# adapter.net
KiCad netlist of a schematic drawn in EAGLE
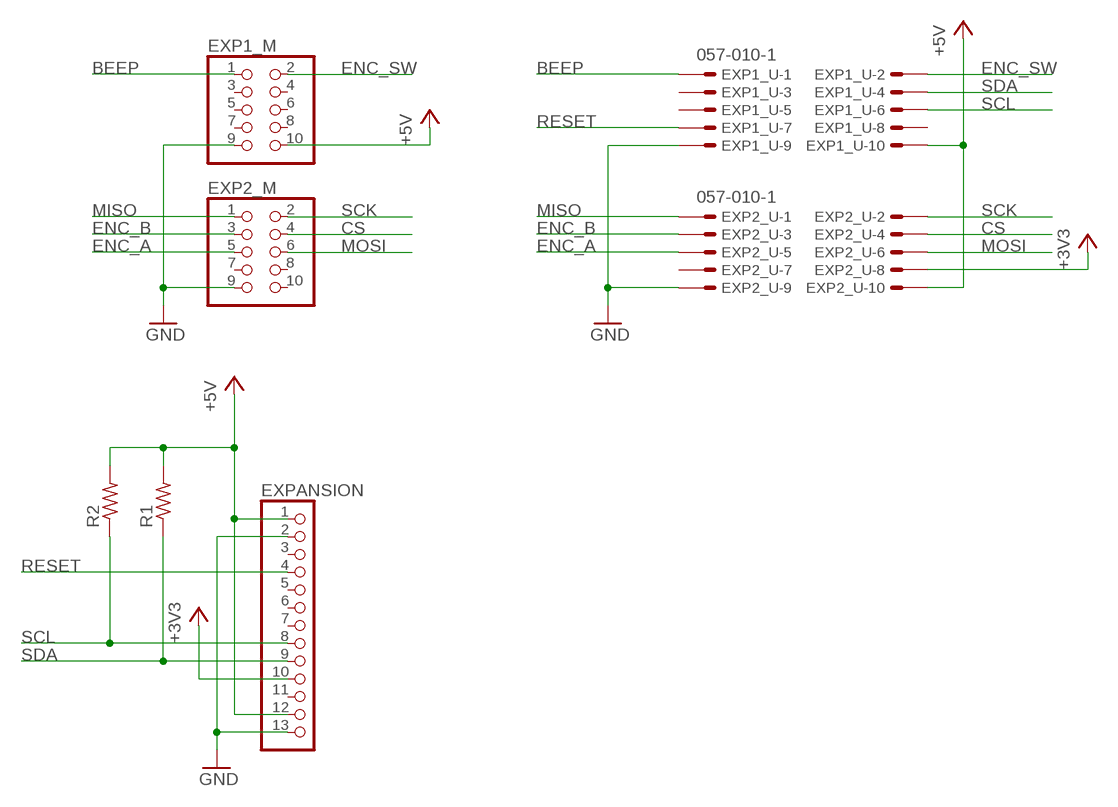
[diagram p0: schematic, sheet 1]

(export (version "E")
  (design (tool "Eeschema 10.0.6"))
  (components
    (comp (ref "EXP1_M")
      (value "PINHD-2X5")
      (footprint "eagle-import:2X05")
      (libsource (lib "eagle-import") (part "PINHD-2X5"))
    )
    (comp (ref "EXP1_U")
      (value "057-010-1")
      (footprint "eagle-import:057-010-1")
      (libsource (lib "eagle-import") (part "057-010-1"))
    )
    (comp (ref "EXP2_M")
      (value "PINHD-2X5")
      (footprint "eagle-import:2X05")
      (libsource (lib "eagle-import") (part "PINHD-2X5"))
    )
    (comp (ref "EXP2_U")
      (value "057-010-1")
      (footprint "eagle-import:057-010-1")
      (libsource (lib "eagle-import") (part "057-010-1"))
    )
    (comp (ref "EXPANSION")
      (value "PINHD-1X13")
      (footprint "eagle-import:1X13")
      (libsource (lib "eagle-import") (part "PINHD-1X13"))
    )
    (comp (ref "R1")
      (value "R-US_0204/7")
      (footprint "eagle-import:0204_7")
      (libsource (lib "eagle-import") (part "R-US_0204/7"))
    )
    (comp (ref "R2")
      (value "R-US_0204/7")
      (footprint "eagle-import:0204_7")
      (libsource (lib "eagle-import") (part "R-US_0204/7"))
    )
  )
  (nets
    (net (code "1") (name "+3V3") (class "Default")
      (node (ref "EXP2_U") (pin "8") (pinfunction "S_8") (pintype "passive"))
      (node (ref "EXPANSION") (pin "10") (pinfunction "10_10") (pintype "passive"))
    )
    (net (code "2") (name "+5V") (class "Default")
      (node (ref "EXP1_M") (pin "10") (pinfunction "10_10") (pintype "passive"))
      (node (ref "EXP1_U") (pin "10") (pinfunction "S_10") (pintype "passive"))
      (node (ref "EXP2_U") (pin "10") (pinfunction "S_10") (pintype "passive"))
      (node (ref "EXPANSION") (pin "1") (pinfunction "1_1") (pintype "passive"))
      (node (ref "EXPANSION") (pin "12") (pinfunction "12_12") (pintype "passive"))
      (node (ref "R1") (pin "2") (pinfunction "2_2") (pintype "passive"))
      (node (ref "R2") (pin "2") (pinfunction "2_2") (pintype "passive"))
    )
    (net (code "3") (name "/BEEP") (class "Default")
      (node (ref "EXP1_M") (pin "1") (pinfunction "1_1") (pintype "passive"))
      (node (ref "EXP1_U") (pin "1") (pinfunction "S_1") (pintype "passive"))
    )
    (net (code "4") (name "/CS") (class "Default")
      (node (ref "EXP2_M") (pin "4") (pinfunction "4_4") (pintype "passive"))
      (node (ref "EXP2_U") (pin "4") (pinfunction "S_4") (pintype "passive"))
    )
    (net (code "5") (name "/ENC_A") (class "Default")
      (node (ref "EXP2_M") (pin "5") (pinfunction "5_5") (pintype "passive"))
      (node (ref "EXP2_U") (pin "5") (pinfunction "S_5") (pintype "passive"))
    )
    (net (code "6") (name "/ENC_B") (class "Default")
      (node (ref "EXP2_M") (pin "3") (pinfunction "3_3") (pintype "passive"))
      (node (ref "EXP2_U") (pin "3") (pinfunction "S_3") (pintype "passive"))
    )
    (net (code "7") (name "/ENC_SW") (class "Default")
      (node (ref "EXP1_M") (pin "2") (pinfunction "2_2") (pintype "passive"))
      (node (ref "EXP1_U") (pin "2") (pinfunction "S_2") (pintype "passive"))
    )
    (net (code "8") (name "/MISO") (class "Default")
      (node (ref "EXP2_M") (pin "1") (pinfunction "1_1") (pintype "passive"))
      (node (ref "EXP2_U") (pin "1") (pinfunction "S_1") (pintype "passive"))
    )
    (net (code "9") (name "/MOSI") (class "Default")
      (node (ref "EXP2_M") (pin "6") (pinfunction "6_6") (pintype "passive"))
      (node (ref "EXP2_U") (pin "6") (pinfunction "S_6") (pintype "passive"))
    )
    (net (code "10") (name "/RESET") (class "Default")
      (node (ref "EXP1_U") (pin "7") (pinfunction "S_7") (pintype "passive"))
      (node (ref "EXPANSION") (pin "4") (pinfunction "4_4") (pintype "passive"))
    )
    (net (code "11") (name "/SCK") (class "Default")
      (node (ref "EXP2_M") (pin "2") (pinfunction "2_2") (pintype "passive"))
      (node (ref "EXP2_U") (pin "2") (pinfunction "S_2") (pintype "passive"))
    )
    (net (code "12") (name "/SCL") (class "Default")
      (node (ref "EXP1_U") (pin "6") (pinfunction "S_6") (pintype "passive"))
      (node (ref "EXPANSION") (pin "8") (pinfunction "8_8") (pintype "passive"))
      (node (ref "R2") (pin "1") (pinfunction "1_1") (pintype "passive"))
    )
    (net (code "13") (name "/SDA") (class "Default")
      (node (ref "EXP1_U") (pin "4") (pinfunction "S_4") (pintype "passive"))
      (node (ref "EXPANSION") (pin "9") (pinfunction "9_9") (pintype "passive"))
      (node (ref "R1") (pin "1") (pinfunction "1_1") (pintype "passive"))
    )
    (net (code "14") (name "GND") (class "Default")
      (node (ref "EXP1_M") (pin "9") (pinfunction "9_9") (pintype "passive"))
      (node (ref "EXP1_U") (pin "9") (pinfunction "S_9") (pintype "passive"))
      (node (ref "EXP2_M") (pin "9") (pinfunction "9_9") (pintype "passive"))
      (node (ref "EXP2_U") (pin "9") (pinfunction "S_9") (pintype "passive"))
      (node (ref "EXPANSION") (pin "13") (pinfunction "13_13") (pintype "passive"))
      (node (ref "EXPANSION") (pin "2") (pinfunction "2_2") (pintype "passive"))
    )
    (net (code "15") (name "unconnected-(EXP1_M-Pad3)") (class "Default")
      (node (ref "EXP1_M") (pin "3") (pinfunction "3_3") (pintype "passive"))
    )
    (net (code "16") (name "unconnected-(EXP1_M-Pad4)") (class "Default")
      (node (ref "EXP1_M") (pin "4") (pinfunction "4_4") (pintype "passive"))
    )
    (net (code "17") (name "unconnected-(EXP1_M-Pad5)") (class "Default")
      (node (ref "EXP1_M") (pin "5") (pinfunction "5_5") (pintype "passive"))
    )
    (net (code "18") (name "unconnected-(EXP1_M-Pad6)") (class "Default")
      (node (ref "EXP1_M") (pin "6") (pinfunction "6_6") (pintype "passive"))
    )
    (net (code "19") (name "unconnected-(EXP1_M-Pad7)") (class "Default")
      (node (ref "EXP1_M") (pin "7") (pinfunction "7_7") (pintype "passive"))
    )
    (net (code "20") (name "unconnected-(EXP1_M-Pad8)") (class "Default")
      (node (ref "EXP1_M") (pin "8") (pinfunction "8_8") (pintype "passive"))
    )
    (net (code "21") (name "unconnected-(EXP1_UD-S-Pad3)") (class "Default")
      (node (ref "EXP1_U") (pin "3") (pinfunction "S_3") (pintype "passive"))
    )
    (net (code "22") (name "unconnected-(EXP1_UF-S-Pad5)") (class "Default")
      (node (ref "EXP1_U") (pin "5") (pinfunction "S_5") (pintype "passive"))
    )
    (net (code "23") (name "unconnected-(EXP1_UI-S-Pad8)") (class "Default")
      (node (ref "EXP1_U") (pin "8") (pinfunction "S_8") (pintype "passive"))
    )
    (net (code "24") (name "unconnected-(EXP2_M-Pad7)") (class "Default")
      (node (ref "EXP2_M") (pin "7") (pinfunction "7_7") (pintype "passive"))
    )
    (net (code "25") (name "unconnected-(EXP2_M-Pad8)") (class "Default")
      (node (ref "EXP2_M") (pin "8") (pinfunction "8_8") (pintype "passive"))
    )
    (net (code "26") (name "unconnected-(EXP2_M-Pad10)") (class "Default")
      (node (ref "EXP2_M") (pin "10") (pinfunction "10_10") (pintype "passive"))
    )
    (net (code "27") (name "unconnected-(EXP2_UH-S-Pad7)") (class "Default")
      (node (ref "EXP2_U") (pin "7") (pinfunction "S_7") (pintype "passive"))
    )
    (net (code "28") (name "unconnected-(EXPANSION-Pad3)") (class "Default")
      (node (ref "EXPANSION") (pin "3") (pinfunction "3_3") (pintype "passive"))
    )
    (net (code "29") (name "unconnected-(EXPANSION-Pad5)") (class "Default")
      (node (ref "EXPANSION") (pin "5") (pinfunction "5_5") (pintype "passive"))
    )
    (net (code "30") (name "unconnected-(EXPANSION-Pad6)") (class "Default")
      (node (ref "EXPANSION") (pin "6") (pinfunction "6_6") (pintype "passive"))
    )
    (net (code "31") (name "unconnected-(EXPANSION-Pad7)") (class "Default")
      (node (ref "EXPANSION") (pin "7") (pinfunction "7_7") (pintype "passive"))
    )
    (net (code "32") (name "unconnected-(EXPANSION-Pad11)") (class "Default")
      (node (ref "EXPANSION") (pin "11") (pinfunction "11_11") (pintype "passive"))
    )
  )
)
